# AS_Node_Transceiver.net
KiCad netlist of a schematic drawn in Altium Designer
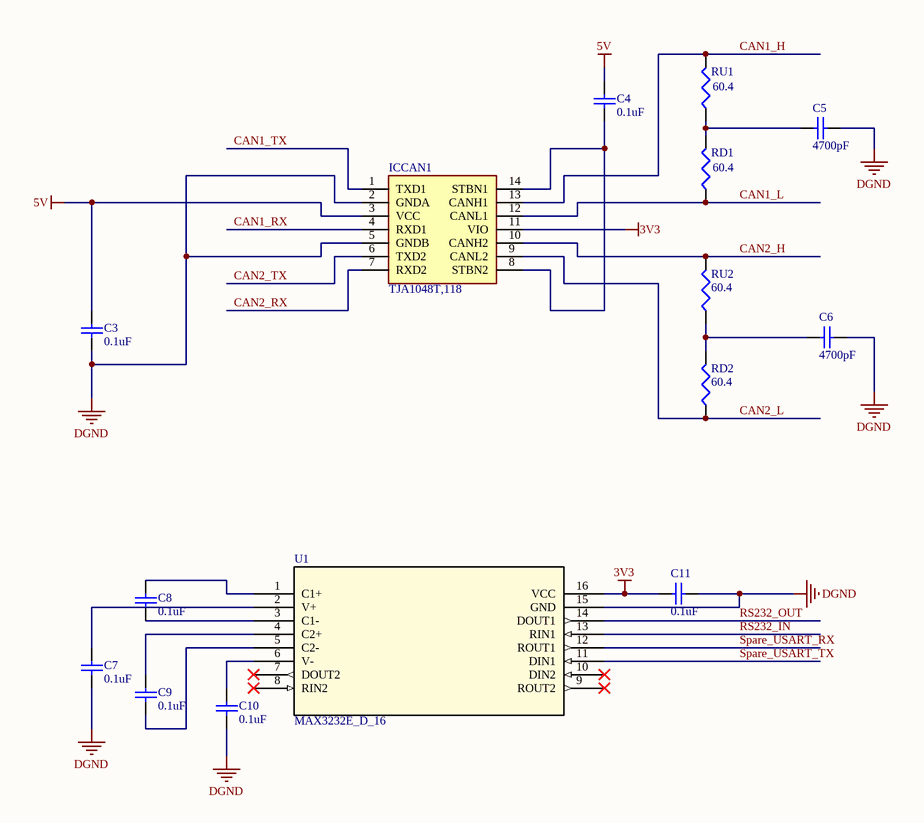
[diagram p0: AS_Node_Transceiver.SchDoc]

(export (version "E")
  (design (tool "Eeschema 10.0.6"))
  (components
    (comp (ref "C3")
      (value "0.1uF")
      (footprint "SMD-0805C")
      (description "Capacitor (Semiconductor SIM Model)")
      (fields (field (name "Comment") "Cap Semi") (field (name "PUBLISHER") "Altium Limited"))
      (libsource (lib "Miscellaneous Devices") (part "Cap Semi"))
    )
    (comp (ref "C4")
      (value "0.1uF")
      (footprint "SMD-0805C")
      (description "Capacitor (Semiconductor SIM Model)")
      (fields (field (name "Comment") "Cap Semi") (field (name "PUBLISHER") "Altium Limited"))
      (libsource (lib "Miscellaneous Devices") (part "Cap Semi"))
    )
    (comp (ref "C5")
      (value "4700pF")
      (footprint "SMD-0805C")
      (description "Capacitor (Semiconductor SIM Model)")
      (fields (field (name "Comment") "Cap Semi") (field (name "PUBLISHER") "Altium Limited"))
      (libsource (lib "Miscellaneous Devices") (part "Cap Semi"))
    )
    (comp (ref "C6")
      (value "4700pF")
      (footprint "SMD-0805C")
      (description "Capacitor (Semiconductor SIM Model)")
      (fields (field (name "Comment") "Cap Semi") (field (name "PUBLISHER") "Altium Limited"))
      (libsource (lib "Miscellaneous Devices") (part "Cap Semi"))
    )
    (comp (ref "C7")
      (value "0.1uF")
      (footprint "SMD-0805C")
      (description "Capacitor (Semiconductor SIM Model)")
      (fields (field (name "Comment") "Cap Semi") (field (name "PUBLISHER") "Altium Limited"))
      (libsource (lib "Miscellaneous Devices") (part "Cap Semi"))
    )
    (comp (ref "C8")
      (value "0.1uF")
      (footprint "SMD-0805C")
      (description "Capacitor (Semiconductor SIM Model)")
      (fields (field (name "Comment") "Cap Semi") (field (name "PUBLISHER") "Altium Limited"))
      (libsource (lib "Miscellaneous Devices") (part "Cap Semi"))
    )
    (comp (ref "C9")
      (value "0.1uF")
      (footprint "SMD-0805C")
      (description "Capacitor (Semiconductor SIM Model)")
      (fields (field (name "Comment") "Cap Semi") (field (name "PUBLISHER") "Altium Limited"))
      (libsource (lib "Miscellaneous Devices") (part "Cap Semi"))
    )
    (comp (ref "C10")
      (value "0.1uF")
      (footprint "SMD-0805C")
      (description "Capacitor (Semiconductor SIM Model)")
      (fields (field (name "Comment") "Cap Semi") (field (name "PUBLISHER") "Altium Limited"))
      (libsource (lib "Miscellaneous Devices") (part "Cap Semi"))
    )
    (comp (ref "C11")
      (value "0.1uF")
      (footprint "SMD-0805C")
      (description "Capacitor (Semiconductor SIM Model)")
      (fields (field (name "Comment") "Cap Semi") (field (name "PUBLISHER") "Altium Limited"))
      (libsource (lib "Miscellaneous Devices") (part "Cap Semi"))
    )
    (comp (ref "ICCAN1")
      (value "TJA1048T,118")
      (footprint "SamacSys:SOIC127P600X175-14N")
      (description "Integrated Circuit")
      (fields (field (name "MOUSER PART NUMBER") "771-TJA1048T118"))
      (libsource (lib "*") (part "TJA1048T,118"))
    )
    (comp (ref "RD1")
      (value "60.4")
      (footprint "SMD-0805-RES")
      (description "Resistor")
      (fields (field (name "Comment") "Res3") (field (name "PUBLISHER") "Altium Limited"))
      (libsource (lib "Miscellaneous Devices") (part "Res3"))
    )
    (comp (ref "RD2")
      (value "60.4")
      (footprint "SMD-0805-RES")
      (description "Resistor")
      (fields (field (name "Comment") "Res3") (field (name "PUBLISHER") "Altium Limited"))
      (libsource (lib "Miscellaneous Devices") (part "Res3"))
    )
    (comp (ref "RU1")
      (value "60.4")
      (footprint "SMD-0805-RES")
      (description "Resistor")
      (fields (field (name "Comment") "Res3") (field (name "PUBLISHER") "Altium Limited"))
      (libsource (lib "Miscellaneous Devices") (part "Res3"))
    )
    (comp (ref "RU2")
      (value "60.4")
      (footprint "SMD-0805-RES")
      (description "Resistor")
      (fields (field (name "Comment") "Res3") (field (name "PUBLISHER") "Altium Limited"))
      (libsource (lib "Miscellaneous Devices") (part "Res3"))
    )
    (comp (ref "U1")
      (value "MAX3232E_D_16")
      (footprint "D16")
      (description "Imported")
      (fields
        (field (name "MANUFACTURER") "Texas Instruments")
        (field (name "GENERIC_PART_NUMBER") "MAX3232E")
      )
      (libsource (lib "MAX3232E") (part "MAX3232E_D_16"))
    )
  )
  (nets
    (net (code "1") (name "/CAN1_H") (class "Default")
      (node (ref "ICCAN1") (pin "13") (pinfunction "CANH1_13") (pintype "passive"))
      (node (ref "RU1") (pin "2") (pinfunction "2_2") (pintype "passive"))
    )
    (net (code "2") (name "/CAN1_L") (class "Default")
      (node (ref "ICCAN1") (pin "12") (pinfunction "CANL1_12") (pintype "passive"))
      (node (ref "RD1") (pin "1") (pinfunction "1_1") (pintype "passive"))
    )
    (net (code "3") (name "/CAN1_RX") (class "Default")
      (node (ref "ICCAN1") (pin "4") (pinfunction "RXD1_4") (pintype "passive"))
    )
    (net (code "4") (name "/CAN1_TX") (class "Default")
      (node (ref "ICCAN1") (pin "1") (pinfunction "TXD1_1") (pintype "passive"))
    )
    (net (code "5") (name "/CAN2_H") (class "Default")
      (node (ref "ICCAN1") (pin "10") (pinfunction "CANH2_10") (pintype "passive"))
      (node (ref "RU2") (pin "2") (pinfunction "2_2") (pintype "passive"))
    )
    (net (code "6") (name "/CAN2_L") (class "Default")
      (node (ref "ICCAN1") (pin "9") (pinfunction "CANL2_9") (pintype "passive"))
      (node (ref "RD2") (pin "1") (pinfunction "1_1") (pintype "passive"))
    )
    (net (code "7") (name "/CAN2_RX") (class "Default")
      (node (ref "ICCAN1") (pin "7") (pinfunction "RXD2_7") (pintype "passive"))
    )
    (net (code "8") (name "/CAN2_TX") (class "Default")
      (node (ref "ICCAN1") (pin "6") (pinfunction "TXD2_6") (pintype "passive"))
    )
    (net (code "9") (name "/RS232_IN") (class "Default")
      (node (ref "U1") (pin "13") (pinfunction "RIN1_13") (pintype "input"))
    )
    (net (code "10") (name "/RS232_OUT") (class "Default")
      (node (ref "U1") (pin "14") (pinfunction "DOUT1_14") (pintype "output"))
    )
    (net (code "11") (name "/Spare_USART_RX") (class "Default")
      (node (ref "U1") (pin "12") (pinfunction "ROUT1_12") (pintype "output"))
    )
    (net (code "12") (name "/Spare_USART_TX") (class "Default")
      (node (ref "U1") (pin "11") (pinfunction "DIN1_11") (pintype "input"))
    )
    (net (code "13") (name "3V3") (class "Default")
      (node (ref "C11") (pin "1") (pinfunction "1_1") (pintype "passive"))
      (node (ref "ICCAN1") (pin "11") (pinfunction "VIO_11") (pintype "passive"))
      (node (ref "U1") (pin "16") (pinfunction "VCC_16") (pintype "power_in"))
    )
    (net (code "14") (name "5V") (class "Default")
      (node (ref "C3") (pin "1") (pinfunction "1_1") (pintype "passive"))
      (node (ref "C4") (pin "1") (pinfunction "1_1") (pintype "passive"))
      (node (ref "ICCAN1") (pin "3") (pinfunction "VCC_3") (pintype "passive"))
    )
    (net (code "15") (name "DGND") (class "Default")
      (node (ref "C10") (pin "2") (pinfunction "2_2") (pintype "passive"))
      (node (ref "C11") (pin "2") (pinfunction "2_2") (pintype "passive"))
      (node (ref "C3") (pin "2") (pinfunction "2_2") (pintype "passive"))
      (node (ref "C5") (pin "2") (pinfunction "2_2") (pintype "passive"))
      (node (ref "C6") (pin "2") (pinfunction "2_2") (pintype "passive"))
      (node (ref "C7") (pin "2") (pinfunction "2_2") (pintype "passive"))
      (node (ref "ICCAN1") (pin "2") (pinfunction "GNDA_2") (pintype "passive"))
      (node (ref "ICCAN1") (pin "5") (pinfunction "GNDB_5") (pintype "passive"))
      (node (ref "U1") (pin "15") (pinfunction "GND_15") (pintype "power_in"))
    )
    (net (code "16") (name "Net-(C5-Pad1)") (class "Default")
      (node (ref "C5") (pin "1") (pinfunction "1_1") (pintype "passive"))
      (node (ref "RD1") (pin "2") (pinfunction "2_2") (pintype "passive"))
      (node (ref "RU1") (pin "1") (pinfunction "1_1") (pintype "passive"))
    )
    (net (code "17") (name "Net-(C6-Pad1)") (class "Default")
      (node (ref "C6") (pin "1") (pinfunction "1_1") (pintype "passive"))
      (node (ref "RD2") (pin "2") (pinfunction "2_2") (pintype "passive"))
      (node (ref "RU2") (pin "1") (pinfunction "1_1") (pintype "passive"))
    )
    (net (code "18") (name "Net-(ICCAN1-STBN1)") (class "Default")
      (node (ref "C4") (pin "2") (pinfunction "2_2") (pintype "passive"))
      (node (ref "ICCAN1") (pin "14") (pinfunction "STBN1_14") (pintype "passive"))
      (node (ref "ICCAN1") (pin "8") (pinfunction "STBN2_8") (pintype "passive"))
    )
    (net (code "19") (name "Net-(U1-C1+)") (class "Default")
      (node (ref "C8") (pin "1") (pinfunction "1_1") (pintype "passive"))
      (node (ref "U1") (pin "1") (pinfunction "C1+_1") (pintype "passive"))
    )
    (net (code "20") (name "Net-(U1-C1-)") (class "Default")
      (node (ref "C8") (pin "2") (pinfunction "2_2") (pintype "passive"))
      (node (ref "U1") (pin "3") (pinfunction "C1-_3") (pintype "passive"))
    )
    (net (code "21") (name "Net-(U1-C2+)") (class "Default")
      (node (ref "C9") (pin "1") (pinfunction "1_1") (pintype "passive"))
      (node (ref "U1") (pin "4") (pinfunction "C2+_4") (pintype "passive"))
    )
    (net (code "22") (name "Net-(U1-C2-)") (class "Default")
      (node (ref "C9") (pin "2") (pinfunction "2_2") (pintype "passive"))
      (node (ref "U1") (pin "5") (pinfunction "C2-_5") (pintype "passive"))
    )
    (net (code "23") (name "Net-(U1-V+)") (class "Default")
      (node (ref "C7") (pin "1") (pinfunction "1_1") (pintype "passive"))
      (node (ref "U1") (pin "2") (pinfunction "V+_2") (pintype "power_in"))
    )
    (net (code "24") (name "Net-(U1-V-)") (class "Default")
      (node (ref "C10") (pin "1") (pinfunction "1_1") (pintype "passive"))
      (node (ref "U1") (pin "6") (pinfunction "V-_6") (pintype "power_in"))
    )
    (net (code "25") (name "unconnected-(U1-DIN2-Pad10)") (class "Default")
      (node (ref "U1") (pin "10") (pinfunction "DIN2_10") (pintype "input+no_connect"))
    )
    (net (code "26") (name "unconnected-(U1-DOUT2-Pad7)") (class "Default")
      (node (ref "U1") (pin "7") (pinfunction "DOUT2_7") (pintype "output+no_connect"))
    )
    (net (code "27") (name "unconnected-(U1-RIN2-Pad8)") (class "Default")
      (node (ref "U1") (pin "8") (pinfunction "RIN2_8") (pintype "input+no_connect"))
    )
    (net (code "28") (name "unconnected-(U1-ROUT2-Pad9)") (class "Default")
      (node (ref "U1") (pin "9") (pinfunction "ROUT2_9") (pintype "output+no_connect"))
    )
  )
)
